# MicroController.net
KiCad netlist of a schematic drawn in Altium Designer
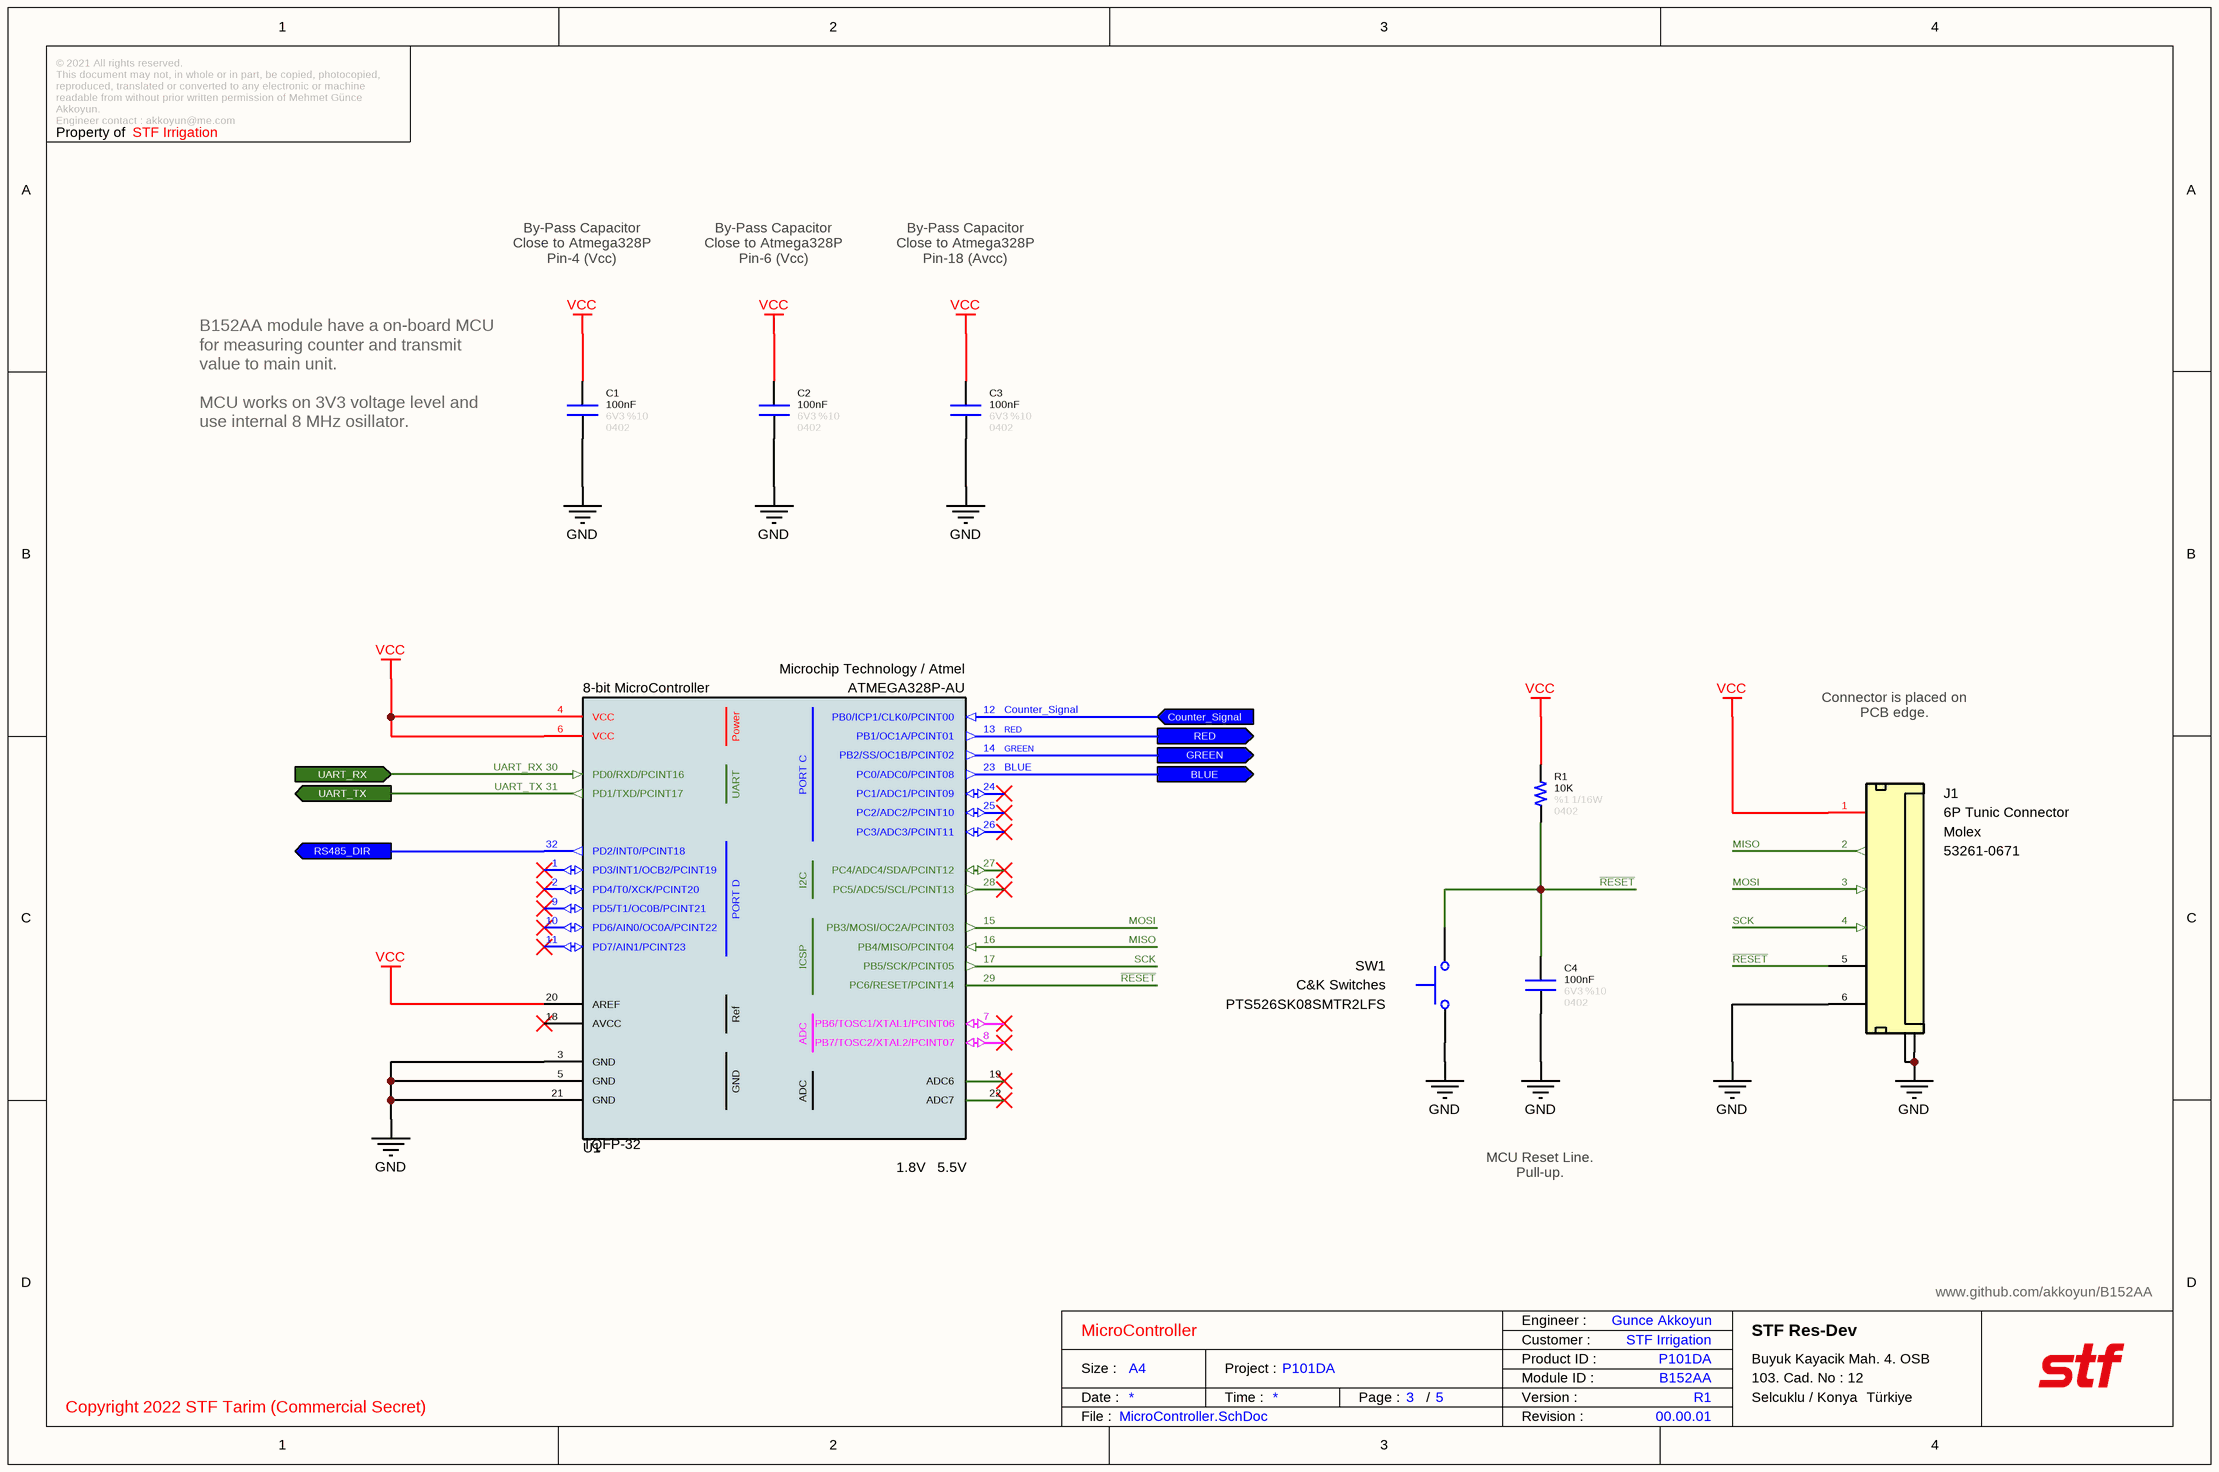
[diagram p0: MicroController.SchDoc]

(export (version "E")
  (design (tool "Eeschema 10.0.6"))
  (components
    (comp (ref "C1")
      (value "100nF")
      (footprint "CAPACITOR_0402")
      (description "Capacitor - 100nF [0402-6V3] (Ceramic)")
      (fields
        (field (name "MANUFACTURER PART NUMBER") "04026D104KAT4A")
        (field (name "TOLERANCE") "%10")
        (field (name "VOLTAGE") "6V3")
        (field (name "CASE") "0402")
        (field (name "Comment") "Capacitor - 100nF [0402] (Ceramic)")
      )
      (libsource (lib "P101DA_Library") (part "Capacitor - 100nF [0402-6V3]"))
    )
    (comp (ref "C2")
      (value "100nF")
      (footprint "CAPACITOR_0402")
      (description "Capacitor - 100nF [0402-6V3] (Ceramic)")
      (fields
        (field (name "MANUFACTURER PART NUMBER") "04026D104KAT4A")
        (field (name "TOLERANCE") "%10")
        (field (name "VOLTAGE") "6V3")
        (field (name "CASE") "0402")
        (field (name "Comment") "Capacitor - 100nF [0402] (Ceramic)")
      )
      (libsource (lib "P101DA_Library") (part "Capacitor - 100nF [0402-6V3]"))
    )
    (comp (ref "C3")
      (value "100nF")
      (footprint "CAPACITOR_0402")
      (description "Capacitor - 100nF [0402-6V3] (Ceramic)")
      (fields
        (field (name "MANUFACTURER PART NUMBER") "04026D104KAT4A")
        (field (name "TOLERANCE") "%10")
        (field (name "VOLTAGE") "6V3")
        (field (name "CASE") "0402")
        (field (name "Comment") "Capacitor - 100nF [0402] (Ceramic)")
      )
      (libsource (lib "P101DA_Library") (part "Capacitor - 100nF [0402-6V3]"))
    )
    (comp (ref "C4")
      (value "100nF")
      (footprint "CAPACITOR_0402")
      (description "Capacitor - 100nF [0402-6V3] (Ceramic)")
      (fields
        (field (name "MANUFACTURER PART NUMBER") "04026D104KAT4A")
        (field (name "TOLERANCE") "%10")
        (field (name "VOLTAGE") "6V3")
        (field (name "CASE") "0402")
        (field (name "Comment") "Capacitor - 100nF [0402] (Ceramic)")
      )
      (libsource (lib "P101DA_Library") (part "Capacitor - 100nF [0402-6V3]"))
    )
    (comp (ref "J1")
      (value "6P Tunic Connector")
      (footprint "Connector_Tunic 6P")
      (description "Mini Tunic Connector with 6P")
      (fields
        (field (name "MANUFACTURER PART NUMBER") "53261-0671")
        (field (name "MANUFACTURER NAME") "Molex")
      )
      (libsource (lib "P101DA_Library") (part "Connector - Mini Tunic 6P (1.25)"))
    )
    (comp (ref "R1")
      (value "10K")
      (footprint "RESISTOR_0402")
      (description "Thick Film Resistors - SMD 1/16 W 10 KOhm 1%")
      (fields
        (field (name "MANUFACTURER PART NUMBER") "CRCW040210K0FKED")
        (field (name "TOLERANCE") "%1")
        (field (name "CASE") "0402")
        (field (name "POWER") "1/16W")
        (field (name "Comment") "10K - 0402 - %1 - 1/16W")
      )
      (libsource (lib "P101DA_Library") (part "Resistor - 10K [0402]"))
    )
    (comp (ref "SW1")
      (value "PTS526SK08SMTR2LFS")
      (footprint "PTS526_Switch")
      (description "Switch Tactile N.O. SPST Flush Round Button Gull Wing 0.05A 12VDC 200000Cycles 2.45N SMD T/R")
      (fields
        (field (name "MANUFACTURER NAME") "C&K Switches")
        (field (name "MANUFACTURER PART NUMBER") "PTS526SK08SMTR2LFS")
      )
      (libsource (lib "P101DA_Library") (part "Switch - Push Button"))
    )
    (comp (ref "U1")
      (value "8-bit MicroController")
      (footprint "TQFN-32")
      (description "8-bit Microcontrollers - MCU 32KB In-system Flash 20MHz 1.8V-5.5V")
      (fields
        (field (name "SUPPLY VOLTAGE - MAX") "5.5V")
        (field (name "SUPPLY VOLTAGE - MIN") "1.8V")
        (field (name "MANUFACTURER NAME") "Microchip Technology / Atmel")
        (field (name "MANUFACTURER PART NUMBER") "ATMEGA328P-AU")
        (field (name "CASE") "TQFP-32")
      )
      (libsource (lib "P101DA_Library") (part "IC - ATMEGA328P-AU"))
    )
  )
  (nets
    (net (code "1") (name "/BLUE") (class "Default")
      (node (ref "U1") (pin "23") (pinfunction "PC0/ADC0/PCINT08_23") (pintype "output"))
    )
    (net (code "2") (name "/Counter_Signal") (class "Default")
      (node (ref "U1") (pin "12") (pinfunction "PB0/ICP1/CLK0/PCINT00_12") (pintype "input"))
    )
    (net (code "3") (name "/GREEN") (class "Default")
      (node (ref "U1") (pin "14") (pinfunction "PB2/SS/OC1B/PCINT02_14") (pintype "output"))
    )
    (net (code "4") (name "/MISO") (class "Default")
      (node (ref "J1") (pin "2") (pinfunction "MISO_2") (pintype "output"))
      (node (ref "U1") (pin "16") (pinfunction "PB4/MISO/PCINT04_16") (pintype "input"))
    )
    (net (code "5") (name "/MOSI") (class "Default")
      (node (ref "J1") (pin "3") (pinfunction "MOSI_3") (pintype "input"))
      (node (ref "U1") (pin "15") (pinfunction "PB3/MOSI/OC2A/PCINT03_15") (pintype "output"))
    )
    (net (code "6") (name "/RED") (class "Default")
      (node (ref "U1") (pin "13") (pinfunction "PB1/OC1A/PCINT01_13") (pintype "output"))
    )
    (net (code "7") (name "/RS485_DIR") (class "Default")
      (node (ref "U1") (pin "32") (pinfunction "PD2/INT0/PCINT18_32") (pintype "output"))
    )
    (net (code "8") (name "/SCK") (class "Default")
      (node (ref "J1") (pin "4") (pinfunction "SCK_4") (pintype "input"))
      (node (ref "U1") (pin "17") (pinfunction "PB5/SCK/PCINT05_17") (pintype "output"))
    )
    (net (code "9") (name "/UART_RX") (class "Default")
      (node (ref "U1") (pin "30") (pinfunction "PD0/RXD/PCINT16_30") (pintype "input"))
    )
    (net (code "10") (name "/UART_TX") (class "Default")
      (node (ref "U1") (pin "31") (pinfunction "PD1/TXD/PCINT17_31") (pintype "output"))
    )
    (net (code "11") (name "/~{RESET}") (class "Default")
      (node (ref "C4") (pin "2") (pinfunction "2_2") (pintype "passive"))
      (node (ref "J1") (pin "5") (pinfunction "RESET_5") (pintype "passive"))
      (node (ref "R1") (pin "1") (pinfunction "1_1") (pintype "passive"))
      (node (ref "SW1") (pin "2") (pinfunction "COM_2") (pintype "passive"))
      (node (ref "U1") (pin "29") (pinfunction "PC6/RESET/PCINT14_29") (pintype "passive"))
    )
    (net (code "12") (name "GND") (class "Default")
      (node (ref "C1") (pin "1") (pinfunction "1_1") (pintype "passive"))
      (node (ref "C2") (pin "1") (pinfunction "1_1") (pintype "passive"))
      (node (ref "C3") (pin "1") (pinfunction "1_1") (pintype "passive"))
      (node (ref "C4") (pin "1") (pinfunction "1_1") (pintype "passive"))
      (node (ref "J1") (pin "6") (pinfunction "GND_6") (pintype "power_in"))
      (node (ref "J1") (pin "7") (pinfunction "GND_7") (pintype "passive"))
      (node (ref "J1") (pin "8") (pinfunction "GND_8") (pintype "passive"))
      (node (ref "SW1") (pin "1") (pinfunction "NC_1") (pintype "passive"))
      (node (ref "U1") (pin "21") (pinfunction "GND_21") (pintype "power_in"))
      (node (ref "U1") (pin "3") (pinfunction "GND_3") (pintype "power_in"))
      (node (ref "U1") (pin "5") (pinfunction "GND_5") (pintype "power_in"))
    )
    (net (code "13") (name "VCC") (class "Default")
      (node (ref "C1") (pin "2") (pinfunction "2_2") (pintype "passive"))
      (node (ref "C2") (pin "2") (pinfunction "2_2") (pintype "passive"))
      (node (ref "C3") (pin "2") (pinfunction "2_2") (pintype "passive"))
      (node (ref "J1") (pin "1") (pinfunction "VCC_1") (pintype "power_in"))
      (node (ref "R1") (pin "2") (pinfunction "2_2") (pintype "passive"))
      (node (ref "U1") (pin "20") (pinfunction "AREF_20") (pintype "passive"))
      (node (ref "U1") (pin "4") (pinfunction "VCC_4") (pintype "power_in"))
      (node (ref "U1") (pin "6") (pinfunction "VCC_6") (pintype "power_in"))
    )
    (net (code "14") (name "unconnected-(U1-ADC6-Pad19)") (class "Default")
      (node (ref "U1") (pin "19") (pinfunction "ADC6_19") (pintype "passive+no_connect"))
    )
    (net (code "15") (name "unconnected-(U1-ADC7-Pad22)") (class "Default")
      (node (ref "U1") (pin "22") (pinfunction "ADC7_22") (pintype "passive+no_connect"))
    )
    (net (code "16") (name "unconnected-(U1-AVCC-Pad18)") (class "Default")
      (node (ref "U1") (pin "18") (pinfunction "AVCC_18") (pintype "passive+no_connect"))
    )
    (net (code "17") (name "unconnected-(U1-PB6{slash}TOSC1{slash}XTAL1{slash}PCINT06-Pad7)") (class "Default")
      (node (ref "U1") (pin "7") (pinfunction "PB6/TOSC1/XTAL1/PCINT06_7") (pintype "bidirectional+no_connect"))
    )
    (net (code "18") (name "unconnected-(U1-PB7{slash}TOSC2{slash}XTAL2{slash}PCINT07-Pad8)") (class "Default")
      (node (ref "U1") (pin "8") (pinfunction "PB7/TOSC2/XTAL2/PCINT07_8") (pintype "bidirectional+no_connect"))
    )
    (net (code "19") (name "unconnected-(U1-PC1{slash}ADC1{slash}PCINT09-Pad24)") (class "Default")
      (node (ref "U1") (pin "24") (pinfunction "PC1/ADC1/PCINT09_24") (pintype "bidirectional+no_connect"))
    )
    (net (code "20") (name "unconnected-(U1-PC2{slash}ADC2{slash}PCINT10-Pad25)") (class "Default")
      (node (ref "U1") (pin "25") (pinfunction "PC2/ADC2/PCINT10_25") (pintype "bidirectional+no_connect"))
    )
    (net (code "21") (name "unconnected-(U1-PC3{slash}ADC3{slash}PCINT11-Pad26)") (class "Default")
      (node (ref "U1") (pin "26") (pinfunction "PC3/ADC3/PCINT11_26") (pintype "bidirectional+no_connect"))
    )
    (net (code "22") (name "unconnected-(U1-PC4{slash}ADC4{slash}SDA{slash}PCINT12-Pad27)") (class "Default")
      (node (ref "U1") (pin "27") (pinfunction "PC4/ADC4/SDA/PCINT12_27") (pintype "bidirectional+no_connect"))
    )
    (net (code "23") (name "unconnected-(U1-PC5{slash}ADC5{slash}SCL{slash}PCINT13-Pad28)") (class "Default")
      (node (ref "U1") (pin "28") (pinfunction "PC5/ADC5/SCL/PCINT13_28") (pintype "output+no_connect"))
    )
    (net (code "24") (name "unconnected-(U1-PD3{slash}INT1{slash}OCB2{slash}PCINT19-Pad1)") (class "Default")
      (node (ref "U1") (pin "1") (pinfunction "PD3/INT1/OCB2/PCINT19_1") (pintype "bidirectional+no_connect"))
    )
    (net (code "25") (name "unconnected-(U1-PD4{slash}T0{slash}XCK{slash}PCINT20-Pad2)") (class "Default")
      (node (ref "U1") (pin "2") (pinfunction "PD4/T0/XCK/PCINT20_2") (pintype "bidirectional+no_connect"))
    )
    (net (code "26") (name "unconnected-(U1-PD5{slash}T1{slash}OC0B{slash}PCINT21-Pad9)") (class "Default")
      (node (ref "U1") (pin "9") (pinfunction "PD5/T1/OC0B/PCINT21_9") (pintype "bidirectional+no_connect"))
    )
    (net (code "27") (name "unconnected-(U1-PD6{slash}AIN0{slash}OC0A{slash}PCINT22-Pad10)") (class "Default")
      (node (ref "U1") (pin "10") (pinfunction "PD6/AIN0/OC0A/PCINT22_10") (pintype "bidirectional+no_connect"))
    )
    (net (code "28") (name "unconnected-(U1-PD7{slash}AIN1{slash}PCINT23-Pad11)") (class "Default")
      (node (ref "U1") (pin "11") (pinfunction "PD7/AIN1/PCINT23_11") (pintype "bidirectional+no_connect"))
    )
  )
)
